# POW.net
KiCad netlist of a schematic drawn in Altium Designer
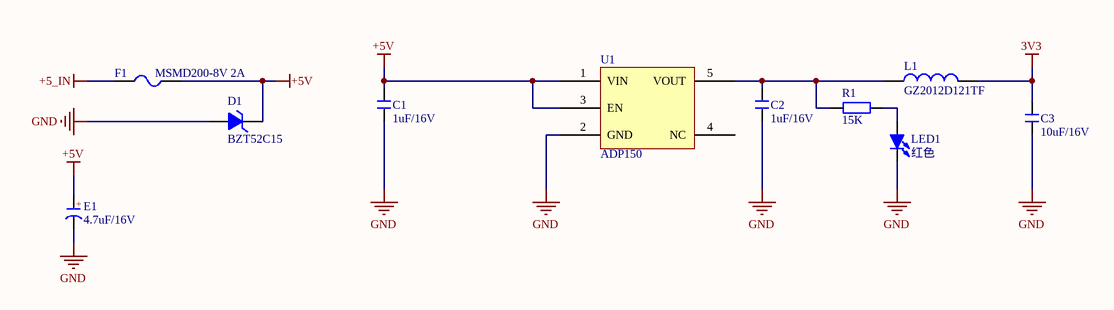
[diagram p0: POW.SchDoc]

(export (version "E")
  (design (tool "Eeschema 10.0.6"))
  (components
    (comp (ref "C1")
      (value "1uF/16V")
      (footprint "C 0402_L")
      (description "贴片电容")
      (libsource (lib "3.1   - 电阻-电容-电感") (part "C"))
    )
    (comp (ref "C2")
      (value "1uF/16V")
      (footprint "C 0402_L")
      (description "贴片电容")
      (libsource (lib "3.1   - 电阻-电容-电感") (part "C"))
    )
    (comp (ref "C3")
      (value "10uF/16V")
      (footprint "C 0603_L")
      (description "贴片电容")
      (libsource (lib "3.1   - 电阻-电容-电感") (part "C"))
    )
    (comp (ref "D1")
      (value "BZT52C15")
      (footprint "SOD-123")
      (libsource (lib "8.1   - 二极管-整流桥") (part "IN4735A"))
    )
    (comp (ref "E1")
      (value "4.7uF/16V")
      (footprint "CD A(3216)")
      (description "聚合物电容 4.7uF/16V")
      (libsource (lib "3.1   - 电阻-电容-电感") (part "C-CD"))
    )
    (comp (ref "F1")
      (value "MSMD200-8V 2A")
      (footprint "FU 0603")
      (description "贴片保险丝")
      (fields (field (name "版权归属") "源创客"))
      (libsource (lib "10.1 - 保险丝-晶振") (part "FU"))
    )
    (comp (ref "L1")
      (value "GZ2012D121TF")
      (footprint "L 0805")
      (description "小功率贴片电感")
      (libsource (lib "3.1   - 电阻-电容-电感") (part "L"))
    )
    (comp (ref "LED1")
      (value "红色")
      (footprint "LED")
      (description "C84267")
      (libsource (lib "9.1   - LED") (part "LED-SMD"))
    )
    (comp (ref "R1")
      (value "15K")
      (footprint "R 0402_L")
      (description "贴片电阻 0402 5%")
      (libsource (lib "3.1   - 电阻-电容-电感") (part "R"))
    )
    (comp (ref "U1")
      (value "ADP150")
      (footprint "SOT23-5")
      (description "ADP150AUJZ-3.3-R7")
      (libsource (lib "2021-06-09_05-08-06") (part "ADP150"))
    )
  )
  (nets
    (net (code "1") (name "+5V") (class "Default")
      (node (ref "C1") (pin "2") (pinfunction "2_2") (pintype "passive"))
      (node (ref "D1") (pin "2") (pinfunction "K_2") (pintype "passive"))
      (node (ref "E1") (pin "1") (pinfunction "A_1") (pintype "passive"))
      (node (ref "F1") (pin "2") (pinfunction "2_2") (pintype "passive"))
      (node (ref "U1") (pin "1") (pinfunction "VIN_1") (pintype "passive"))
      (node (ref "U1") (pin "3") (pinfunction "EN_3") (pintype "passive"))
    )
    (net (code "2") (name "+5_IN") (class "Default")
      (node (ref "F1") (pin "1") (pinfunction "1_1") (pintype "passive"))
    )
    (net (code "3") (name "3V3") (class "Default")
      (node (ref "C3") (pin "2") (pinfunction "2_2") (pintype "passive"))
      (node (ref "L1") (pin "2") (pinfunction "2_2") (pintype "passive"))
    )
    (net (code "4") (name "GND") (class "Default")
      (node (ref "C1") (pin "1") (pinfunction "1_1") (pintype "passive"))
      (node (ref "C2") (pin "1") (pinfunction "1_1") (pintype "passive"))
      (node (ref "C3") (pin "1") (pinfunction "1_1") (pintype "passive"))
      (node (ref "D1") (pin "1") (pinfunction "A_1") (pintype "passive"))
      (node (ref "E1") (pin "2") (pinfunction "K_2") (pintype "passive"))
      (node (ref "LED1") (pin "2") (pinfunction "K_2") (pintype "passive"))
      (node (ref "U1") (pin "2") (pinfunction "GND_2") (pintype "passive"))
    )
    (net (code "5") (name "Net-(LED1-A)") (class "Default")
      (node (ref "LED1") (pin "1") (pinfunction "A_1") (pintype "passive"))
      (node (ref "R1") (pin "2") (pinfunction "2_2") (pintype "passive"))
    )
    (net (code "6") (name "Net-(U1-VOUT)") (class "Default")
      (node (ref "C2") (pin "2") (pinfunction "2_2") (pintype "passive"))
      (node (ref "L1") (pin "1") (pinfunction "1_1") (pintype "passive"))
      (node (ref "R1") (pin "1") (pinfunction "1_1") (pintype "passive"))
      (node (ref "U1") (pin "5") (pinfunction "VOUT_5") (pintype "passive"))
    )
    (net (code "7") (name "unconnected-(U1-NC-Pad4)") (class "Default")
      (node (ref "U1") (pin "4") (pinfunction "NC_4") (pintype "passive"))
    )
  )
)
